# Addon-mapleCUx_HM-RFM69-RFM95-V12-001.net
KiCad netlist of a schematic drawn in EAGLE
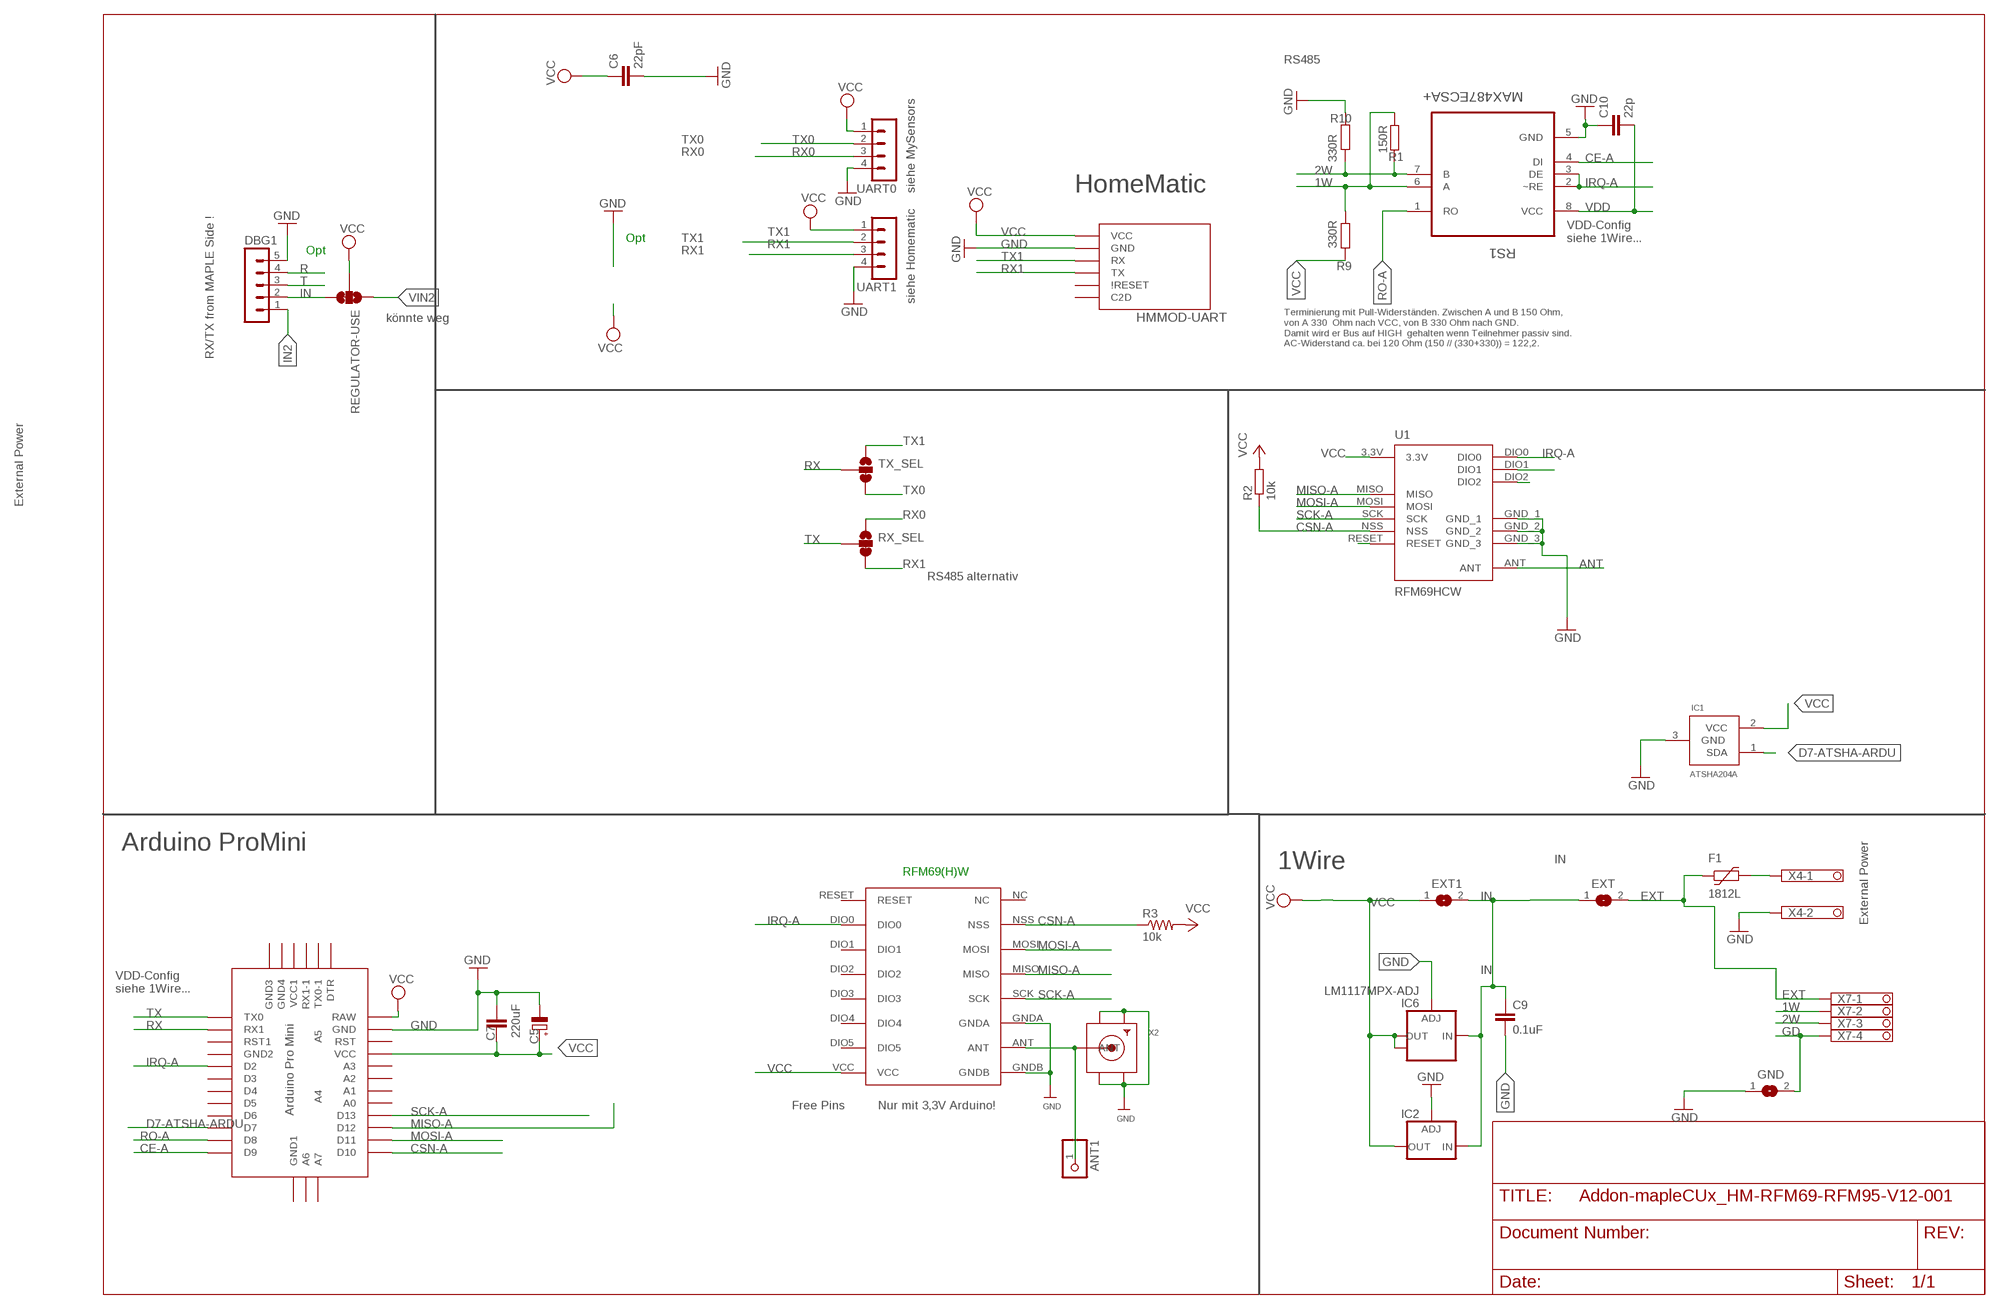
[diagram p0: schematic, sheet 1]

(export (version "E")
  (design (tool "Eeschema 10.0.6"))
  (components
    (comp (ref "ANT1")
      (value "PINHD-1X1")
      (footprint "eagle-import:1X01")
      (libsource (lib "eagle-import") (part "PINHD-1X1"))
    )
    (comp (ref "C5")
      (value "220uF")
      (footprint "eagle-import:E5-8,5")
      (libsource (lib "eagle-import") (part "CPOL-EUE5-8.5"))
    )
    (comp (ref "C6")
      (value "22pF")
      (footprint "eagle-import:C0805")
      (libsource (lib "eagle-import") (part "C-EUC0805"))
    )
    (comp (ref "C7")
      (value "C-EUC1812")
      (footprint "eagle-import:C1812")
      (libsource (lib "eagle-import") (part "C-EUC1812"))
    )
    (comp (ref "C9")
      (value "0.1uF")
      (footprint "eagle-import:C1206")
      (libsource (lib "eagle-import") (part "C-EUC1206"))
    )
    (comp (ref "C10")
      (value "22p")
      (footprint "eagle-import:C0805")
      (libsource (lib "eagle-import") (part "C-EUC0805"))
    )
    (comp (ref "DBG1")
      (value "MA05-1")
      (footprint "eagle-import:MA05-1")
      (libsource (lib "eagle-import") (part "MA05-1"))
    )
    (comp (ref "EXT") (value "SJ") (footprint "eagle-import:SJ") (libsource (lib "eagle-import") (part "SJ")))
    (comp (ref "EXT1")
      (value "SJ")
      (footprint "eagle-import:SJ")
      (libsource (lib "eagle-import") (part "SJ"))
    )
    (comp (ref "F1")
      (value "1812L")
      (footprint "eagle-import:1812L")
      (libsource (lib "eagle-import") (part "1812L"))
    )
    (comp (ref "GND") (value "SJ") (footprint "eagle-import:SJ") (libsource (lib "eagle-import") (part "SJ")))
    (comp (ref "HMMOD-UART")
      (value "HM-MOD-UARTDIL")
      (footprint "eagle-import:HM-MOD-UART-DIL")
      (libsource (lib "eagle-import") (part "HM-MOD-UARTDIL"))
    )
    (comp (ref "IC1")
      (value "ATSHA204A")
      (footprint "eagle-import:SOT23")
      (libsource (lib "eagle-import") (part "ATSHA204A"))
    )
    (comp (ref "IC2")
      (value "LD117ADT50TR")
      (footprint "eagle-import:DPACK")
      (libsource (lib "eagle-import") (part "LD117A?DT50TR"))
    )
    (comp (ref "IC6")
      (value "LM1117MPX-ADJ")
      (footprint "eagle-import:SOT223")
      (libsource (lib "eagle-import") (part "LM1117MPX-ADJ"))
    )
    (comp (ref "R1")
      (value "150R")
      (footprint "eagle-import:R0805")
      (libsource (lib "eagle-import") (part "R-EU_R0805"))
    )
    (comp (ref "R2")
      (value "10k")
      (footprint "eagle-import:M0805")
      (libsource (lib "eagle-import") (part "R-EU_M0805"))
    )
    (comp (ref "R3")
      (value "10k")
      (footprint "eagle-import:0805")
      (libsource (lib "eagle-import") (part "RESISTOR0805-RES"))
    )
    (comp (ref "R9")
      (value "330R")
      (footprint "eagle-import:R0805")
      (libsource (lib "eagle-import") (part "R-EU_R0805"))
    )
    (comp (ref "R10")
      (value "330R")
      (footprint "eagle-import:R0805")
      (libsource (lib "eagle-import") (part "R-EU_R0805"))
    )
    (comp (ref "REGULATOR-USE")
      (value "JUMPER-SMT_3_1-NC_TRACE_SILK")
      (footprint "eagle-import:SMT-JUMPER_3_1-NC_TRACE_SILK")
      (libsource (lib "eagle-import") (part "JUMPER-SMT_3_1-NC_TRACE_SILK"))
    )
    (comp (ref "RFM69W")
      (value "RFM69HW")
      (footprint "eagle-import:RFM")
      (libsource (lib "eagle-import") (part "RFM69HW"))
    )
    (comp (ref "RS1")
      (value "MAX487ECSA+")
      (footprint "eagle-import:SOIC127P600X175-8N")
      (libsource (lib "eagle-import") (part "MAX487ECSA+"))
    )
    (comp (ref "RX_SEL")
      (value "JUMPER-SMT_3_1-NC_TRACE_SILK")
      (footprint "eagle-import:SMT-JUMPER_3_1-NC_TRACE_SILK")
      (libsource (lib "eagle-import") (part "JUMPER-SMT_3_1-NC_TRACE_SILK"))
    )
    (comp (ref "TX_SEL")
      (value "JUMPER-SMT_3_1-NC_TRACE_SILK")
      (footprint "eagle-import:SMT-JUMPER_3_1-NC_TRACE_SILK")
      (libsource (lib "eagle-import") (part "JUMPER-SMT_3_1-NC_TRACE_SILK"))
    )
    (comp (ref "U$2")
      (value "ABK-PRO-MINI")
      (footprint "eagle-import:ABK-PRO-MINI")
      (libsource (lib "eagle-import") (part "ABK-PRO-MINI"))
    )
    (comp (ref "U1")
      (value "RFM69HCW")
      (footprint "eagle-import:RFM69HCW-XXXS2")
      (libsource (lib "eagle-import") (part "RFM69HCW"))
    )
    (comp (ref "UART0")
      (value "MA04-1")
      (footprint "eagle-import:MA04-1")
      (libsource (lib "eagle-import") (part "MA04-1"))
    )
    (comp (ref "UART1")
      (value "MA04-1")
      (footprint "eagle-import:MA04-1")
      (libsource (lib "eagle-import") (part "MA04-1"))
    )
    (comp (ref "X2")
      (value "SMACONNECTOR_EDGE")
      (footprint "eagle-import:SMA_EDGELAUNCH")
      (libsource (lib "eagle-import") (part "SMACONNECTOR_EDGE"))
    )
    (comp (ref "X4")
      (value "1751248")
      (footprint "eagle-import:1751248")
      (libsource (lib "eagle-import") (part "1751248"))
    )
    (comp (ref "X7")
      (value "1751264")
      (footprint "eagle-import:1751264")
      (libsource (lib "eagle-import") (part "1751264"))
    )
  )
  (nets
    (net (code "1") (name "/1W") (class "Default")
      (node (ref "R1") (pin "1") (pinfunction "1_1") (pintype "passive"))
      (node (ref "R9") (pin "2") (pinfunction "2_2") (pintype "passive"))
      (node (ref "RS1") (pin "6") (pinfunction "A_6") (pintype "bidirectional"))
      (node (ref "X7") (pin "2") (pinfunction "K_2") (pintype "passive"))
    )
    (net (code "2") (name "/2W") (class "Default")
      (node (ref "R1") (pin "2") (pinfunction "2_2") (pintype "passive"))
      (node (ref "R10") (pin "1") (pinfunction "1_1") (pintype "passive"))
      (node (ref "RS1") (pin "7") (pinfunction "B_7") (pintype "bidirectional"))
      (node (ref "X7") (pin "3") (pinfunction "K_3") (pintype "passive"))
    )
    (net (code "3") (name "/ANT") (class "Default")
      (node (ref "ANT1") (pin "1") (pinfunction "1_1") (pintype "passive"))
      (node (ref "RFM69W") (pin "ANT") (pinfunction "ANT_ANT") (pintype "bidirectional"))
      (node (ref "U1") (pin "ANT") (pinfunction "ANT_ANT") (pintype "passive"))
      (node (ref "X2") (pin "P") (pinfunction "ANT_P") (pintype "bidirectional"))
    )
    (net (code "4") (name "/CE-A") (class "Default")
      (node (ref "RS1") (pin "4") (pinfunction "DI_4") (pintype "input"))
      (node (ref "U$2") (pin "D9") (pinfunction "D9_D9") (pintype "bidirectional"))
    )
    (net (code "5") (name "/CSN-A") (class "Default")
      (node (ref "R2") (pin "1") (pinfunction "1_1") (pintype "passive"))
      (node (ref "R3") (pin "1") (pinfunction "1_1") (pintype "passive"))
      (node (ref "RFM69W") (pin "NSS") (pinfunction "NSS_NSS") (pintype "bidirectional"))
      (node (ref "U$2") (pin "D10") (pinfunction "D10_D10") (pintype "bidirectional"))
      (node (ref "U1") (pin "NSS") (pinfunction "NSS_NSS") (pintype "input"))
    )
    (net (code "6") (name "/EXT") (class "Default")
      (node (ref "EXT") (pin "2") (pinfunction "2_2") (pintype "passive"))
      (node (ref "F1") (pin "P$1") (pinfunction "1_P$1") (pintype "passive"))
      (node (ref "X7") (pin "1") (pinfunction "K_1") (pintype "passive"))
    )
    (net (code "7") (name "/GD") (class "Default")
      (node (ref "GND") (pin "2") (pinfunction "2_2") (pintype "passive"))
      (node (ref "X7") (pin "4") (pinfunction "K_4") (pintype "passive"))
    )
    (net (code "8") (name "/IN") (class "Default")
      (node (ref "C9") (pin "1") (pinfunction "1_1") (pintype "passive"))
      (node (ref "DBG1") (pin "2") (pinfunction "2_2") (pintype "passive"))
      (node (ref "EXT") (pin "1") (pinfunction "1_1") (pintype "passive"))
      (node (ref "EXT1") (pin "2") (pinfunction "2_2") (pintype "passive"))
      (node (ref "IC2") (pin "3") (pinfunction "IN_3") (pintype "input"))
      (node (ref "IC6") (pin "3") (pinfunction "IN_3") (pintype "input"))
      (node (ref "REGULATOR-USE") (pin "3") (pinfunction "3_3") (pintype "passive"))
    )
    (net (code "9") (name "/IRQ-A") (class "Default")
      (node (ref "RFM69W") (pin "DIO0") (pinfunction "DIO0_DIO0") (pintype "bidirectional"))
      (node (ref "RS1") (pin "2") (pinfunction "~{RE}_2") (pintype "input"))
      (node (ref "RS1") (pin "3") (pinfunction "DE_3") (pintype "input"))
      (node (ref "U$2") (pin "D2") (pinfunction "D2_D2") (pintype "bidirectional"))
      (node (ref "U1") (pin "DIO0") (pinfunction "DIO0_DIO0") (pintype "bidirectional"))
    )
    (net (code "10") (name "/MISO-A") (class "Default")
      (node (ref "RFM69W") (pin "MISO") (pinfunction "MISO_MISO") (pintype "bidirectional"))
      (node (ref "U$2") (pin "D12") (pinfunction "D12_D12") (pintype "bidirectional"))
      (node (ref "U1") (pin "MISO") (pinfunction "MISO_MISO") (pintype "bidirectional"))
    )
    (net (code "11") (name "/MOSI-A") (class "Default")
      (node (ref "RFM69W") (pin "MOSI") (pinfunction "MOSI_MOSI") (pintype "bidirectional"))
      (node (ref "U$2") (pin "D11") (pinfunction "D11_D11") (pintype "bidirectional"))
      (node (ref "U1") (pin "MOSI") (pinfunction "MOSI_MOSI") (pintype "input"))
    )
    (net (code "12") (name "/R") (class "Default")
      (node (ref "DBG1") (pin "4") (pinfunction "4_4") (pintype "passive"))
    )
    (net (code "13") (name "/RX") (class "Default")
      (node (ref "TX_SEL") (pin "2") (pinfunction "2_2") (pintype "passive"))
      (node (ref "U$2") (pin "RX1") (pinfunction "RX1_RX1") (pintype "bidirectional"))
    )
    (net (code "14") (name "/RX0") (class "Default")
      (node (ref "RX_SEL") (pin "1") (pinfunction "1_1") (pintype "passive"))
      (node (ref "UART0") (pin "3") (pinfunction "3_3") (pintype "passive"))
    )
    (net (code "15") (name "/RX1") (class "Default")
      (node (ref "HMMOD-UART") (pin "5") (pinfunction "TX_5") (pintype "bidirectional"))
      (node (ref "RX_SEL") (pin "3") (pinfunction "3_3") (pintype "passive"))
      (node (ref "UART1") (pin "3") (pinfunction "3_3") (pintype "passive"))
    )
    (net (code "16") (name "/SCK-A") (class "Default")
      (node (ref "RFM69W") (pin "SCK") (pinfunction "SCK_SCK") (pintype "bidirectional"))
      (node (ref "U$2") (pin "D13") (pinfunction "D13_D13") (pintype "bidirectional"))
      (node (ref "U1") (pin "SCK") (pinfunction "SCK_SCK") (pintype "input"))
    )
    (net (code "17") (name "/T") (class "Default")
      (node (ref "DBG1") (pin "3") (pinfunction "3_3") (pintype "passive"))
    )
    (net (code "18") (name "/TX") (class "Default")
      (node (ref "RX_SEL") (pin "2") (pinfunction "2_2") (pintype "passive"))
      (node (ref "U$2") (pin "TX0") (pinfunction "TX0_TX0") (pintype "bidirectional"))
    )
    (net (code "19") (name "/TX0") (class "Default")
      (node (ref "TX_SEL") (pin "3") (pinfunction "3_3") (pintype "passive"))
      (node (ref "UART0") (pin "2") (pinfunction "2_2") (pintype "passive"))
    )
    (net (code "20") (name "/TX1") (class "Default")
      (node (ref "HMMOD-UART") (pin "6") (pinfunction "RX_6") (pintype "bidirectional"))
      (node (ref "TX_SEL") (pin "1") (pinfunction "1_1") (pintype "passive"))
      (node (ref "UART1") (pin "2") (pinfunction "2_2") (pintype "passive"))
    )
    (net (code "21") (name "/VDD") (class "Default")
      (node (ref "C10") (pin "2") (pinfunction "2_2") (pintype "passive"))
      (node (ref "RS1") (pin "8") (pinfunction "VCC_8") (pintype "power_in"))
    )
    (net (code "22") (name "D7-ATSHA-ARDU") (class "Default")
      (node (ref "IC1") (pin "1") (pinfunction "SDA_1") (pintype "bidirectional"))
      (node (ref "U$2") (pin "D7") (pinfunction "D7_D7") (pintype "bidirectional"))
    )
    (net (code "23") (name "GND") (class "Default")
      (node (ref "C10") (pin "1") (pinfunction "1_1") (pintype "passive"))
      (node (ref "C5") (pin "-") (pinfunction "-_-") (pintype "passive"))
      (node (ref "C6") (pin "2") (pinfunction "2_2") (pintype "passive"))
      (node (ref "C7") (pin "1") (pinfunction "1_1") (pintype "passive"))
      (node (ref "C9") (pin "2") (pinfunction "2_2") (pintype "passive"))
      (node (ref "DBG1") (pin "5") (pinfunction "5_5") (pintype "passive"))
      (node (ref "GND") (pin "1") (pinfunction "1_1") (pintype "passive"))
      (node (ref "HMMOD-UART") (pin "2") (pinfunction "GND_2") (pintype "power_in"))
      (node (ref "IC1") (pin "3") (pinfunction "GND_3") (pintype "bidirectional"))
      (node (ref "IC2") (pin "1") (pinfunction "ADJ_1") (pintype "input"))
      (node (ref "IC6") (pin "1") (pinfunction "ADJ_1") (pintype "input"))
      (node (ref "R10") (pin "2") (pinfunction "2_2") (pintype "passive"))
      (node (ref "RFM69W") (pin "GNDA") (pinfunction "GNDA_GNDA") (pintype "bidirectional"))
      (node (ref "RFM69W") (pin "GNDB") (pinfunction "GNDB_GNDB") (pintype "bidirectional"))
      (node (ref "RS1") (pin "5") (pinfunction "GND_5") (pintype "passive"))
      (node (ref "U$2") (pin "GND") (pinfunction "GND_GND") (pintype "bidirectional"))
      (node (ref "U1") (pin "GND_1") (pinfunction "GND_1_GND_1") (pintype "power_in"))
      (node (ref "U1") (pin "GND_2") (pinfunction "GND_2_GND_2") (pintype "power_in"))
      (node (ref "U1") (pin "GND_3") (pinfunction "GND_3_GND_3") (pintype "power_in"))
      (node (ref "UART0") (pin "4") (pinfunction "4_4") (pintype "passive"))
      (node (ref "UART1") (pin "4") (pinfunction "4_4") (pintype "passive"))
      (node (ref "X2") (pin "GND@1") (pinfunction "GND4_GND@1") (pintype "power_in"))
      (node (ref "X2") (pin "GND@2") (pinfunction "GND3_GND@2") (pintype "power_in"))
      (node (ref "X2") (pin "GND@3") (pinfunction "GND2_GND@3") (pintype "power_in"))
      (node (ref "X2") (pin "GND@4") (pinfunction "GND1_GND@4") (pintype "power_in"))
      (node (ref "X4") (pin "2") (pinfunction "K_2") (pintype "passive"))
    )
    (net (code "24") (name "IN2") (class "Default")
      (node (ref "DBG1") (pin "1") (pinfunction "1_1") (pintype "passive"))
    )
    (net (code "25") (name "Net-(F1-2)") (class "Default")
      (node (ref "F1") (pin "P$2") (pinfunction "2_P$2") (pintype "passive"))
      (node (ref "X4") (pin "1") (pinfunction "K_1") (pintype "passive"))
    )
    (net (code "26") (name "RO-A") (class "Default")
      (node (ref "RS1") (pin "1") (pinfunction "RO_1") (pintype "output"))
      (node (ref "U$2") (pin "D8") (pinfunction "D8_D8") (pintype "bidirectional"))
    )
    (net (code "27") (name "VCC") (class "Default")
      (node (ref "C5") (pin "+") (pinfunction "+_+") (pintype "passive"))
      (node (ref "C6") (pin "1") (pinfunction "1_1") (pintype "passive"))
      (node (ref "C7") (pin "2") (pinfunction "2_2") (pintype "passive"))
      (node (ref "EXT1") (pin "1") (pinfunction "1_1") (pintype "passive"))
      (node (ref "HMMOD-UART") (pin "1") (pinfunction "VCC_1") (pintype "power_in"))
      (node (ref "IC1") (pin "2") (pinfunction "VCC_2") (pintype "bidirectional"))
      (node (ref "IC2") (pin "4") (pinfunction "OUT_4") (pintype "passive"))
      (node (ref "IC6") (pin "2") (pinfunction "OUT_2") (pintype "passive"))
      (node (ref "IC6") (pin "TAB") (pinfunction "OUT1_TAB") (pintype "passive"))
      (node (ref "R2") (pin "2") (pinfunction "2_2") (pintype "passive"))
      (node (ref "R3") (pin "2") (pinfunction "2_2") (pintype "passive"))
      (node (ref "R9") (pin "1") (pinfunction "1_1") (pintype "passive"))
      (node (ref "REGULATOR-USE") (pin "2") (pinfunction "2_2") (pintype "passive"))
      (node (ref "RFM69W") (pin "VCC") (pinfunction "VCC_VCC") (pintype "bidirectional"))
      (node (ref "U$2") (pin "RAW") (pinfunction "RAW_RAW") (pintype "bidirectional"))
      (node (ref "U$2") (pin "VCC") (pinfunction "VCC_VCC") (pintype "bidirectional"))
      (node (ref "U1") (pin "3.3V") (pinfunction "3.3V_3.3V") (pintype "power_in"))
      (node (ref "UART0") (pin "1") (pinfunction "1_1") (pintype "passive"))
      (node (ref "UART1") (pin "1") (pinfunction "1_1") (pintype "passive"))
    )
    (net (code "28") (name "VIN2") (class "Default")
      (node (ref "REGULATOR-USE") (pin "1") (pinfunction "1_1") (pintype "passive"))
    )
    (net (code "29") (name "unconnected-(HMMOD-UART-C2D-Pad3)") (class "Default")
      (node (ref "HMMOD-UART") (pin "3") (pinfunction "C2D_3") (pintype "bidirectional"))
    )
    (net (code "30") (name "unconnected-(HMMOD-UART-\\~{RESET}-Pad4)") (class "Default")
      (node (ref "HMMOD-UART") (pin "4") (pinfunction "\\~{RESET}_4") (pintype "bidirectional"))
    )
    (net (code "31") (name "unconnected-(RFM69W-PadDIO1)") (class "Default")
      (node (ref "RFM69W") (pin "DIO1") (pinfunction "DIO1_DIO1") (pintype "bidirectional"))
    )
    (net (code "32") (name "unconnected-(RFM69W-PadDIO2)") (class "Default")
      (node (ref "RFM69W") (pin "DIO2") (pinfunction "DIO2_DIO2") (pintype "bidirectional"))
    )
    (net (code "33") (name "unconnected-(RFM69W-PadDIO3)") (class "Default")
      (node (ref "RFM69W") (pin "DIO3") (pinfunction "DIO3_DIO3") (pintype "bidirectional"))
    )
    (net (code "34") (name "unconnected-(RFM69W-PadDIO4)") (class "Default")
      (node (ref "RFM69W") (pin "DIO4") (pinfunction "DIO4_DIO4") (pintype "bidirectional"))
    )
    (net (code "35") (name "unconnected-(RFM69W-PadDIO5)") (class "Default")
      (node (ref "RFM69W") (pin "DIO5") (pinfunction "DIO5_DIO5") (pintype "bidirectional"))
    )
    (net (code "36") (name "unconnected-(RFM69W-PadNC)") (class "Default")
      (node (ref "RFM69W") (pin "NC") (pinfunction "NC_NC") (pintype "bidirectional"))
    )
    (net (code "37") (name "unconnected-(RFM69W-PadRESET)") (class "Default")
      (node (ref "RFM69W") (pin "RESET") (pinfunction "RESET_RESET") (pintype "bidirectional"))
    )
    (net (code "38") (name "unconnected-(U$2-GND1-PadGND4)") (class "Default")
      (node (ref "U$2") (pin "GND4") (pinfunction "GND1_GND4") (pintype "bidirectional"))
    )
    (net (code "39") (name "unconnected-(U$2-GND2-PadGND1)") (class "Default")
      (node (ref "U$2") (pin "GND1") (pinfunction "GND2_GND1") (pintype "bidirectional"))
    )
    (net (code "40") (name "unconnected-(U$2-GND3-PadGND2)") (class "Default")
      (node (ref "U$2") (pin "GND2") (pinfunction "GND3_GND2") (pintype "bidirectional"))
    )
    (net (code "41") (name "unconnected-(U$2-GND4-PadGND3)") (class "Default")
      (node (ref "U$2") (pin "GND3") (pinfunction "GND4_GND3") (pintype "bidirectional"))
    )
    (net (code "42") (name "unconnected-(U$2-PadA0)") (class "Default")
      (node (ref "U$2") (pin "A0") (pinfunction "A0_A0") (pintype "bidirectional"))
    )
    (net (code "43") (name "unconnected-(U$2-PadA1)") (class "Default")
      (node (ref "U$2") (pin "A1") (pinfunction "A1_A1") (pintype "bidirectional"))
    )
    (net (code "44") (name "unconnected-(U$2-PadA2)") (class "Default")
      (node (ref "U$2") (pin "A2") (pinfunction "A2_A2") (pintype "bidirectional"))
    )
    (net (code "45") (name "unconnected-(U$2-PadA3)") (class "Default")
      (node (ref "U$2") (pin "A3") (pinfunction "A3_A3") (pintype "bidirectional"))
    )
    (net (code "46") (name "unconnected-(U$2-PadA4)") (class "Default")
      (node (ref "U$2") (pin "A4") (pinfunction "A4_A4") (pintype "bidirectional"))
    )
    (net (code "47") (name "unconnected-(U$2-PadA5)") (class "Default")
      (node (ref "U$2") (pin "A5") (pinfunction "A5_A5") (pintype "bidirectional"))
    )
    (net (code "48") (name "unconnected-(U$2-PadA6)") (class "Default")
      (node (ref "U$2") (pin "A6") (pinfunction "A6_A6") (pintype "bidirectional"))
    )
    (net (code "49") (name "unconnected-(U$2-PadA7)") (class "Default")
      (node (ref "U$2") (pin "A7") (pinfunction "A7_A7") (pintype "bidirectional"))
    )
    (net (code "50") (name "unconnected-(U$2-PadD3)") (class "Default")
      (node (ref "U$2") (pin "D3") (pinfunction "D3_D3") (pintype "bidirectional"))
    )
    (net (code "51") (name "unconnected-(U$2-PadD4)") (class "Default")
      (node (ref "U$2") (pin "D4") (pinfunction "D4_D4") (pintype "bidirectional"))
    )
    (net (code "52") (name "unconnected-(U$2-PadD5)") (class "Default")
      (node (ref "U$2") (pin "D5") (pinfunction "D5_D5") (pintype "bidirectional"))
    )
    (net (code "53") (name "unconnected-(U$2-PadD6)") (class "Default")
      (node (ref "U$2") (pin "D6") (pinfunction "D6_D6") (pintype "bidirectional"))
    )
    (net (code "54") (name "unconnected-(U$2-PadDTR)") (class "Default")
      (node (ref "U$2") (pin "DTR") (pinfunction "DTR_DTR") (pintype "bidirectional"))
    )
    (net (code "55") (name "unconnected-(U$2-PadRST)") (class "Default")
      (node (ref "U$2") (pin "RST") (pinfunction "RST_RST") (pintype "bidirectional"))
    )
    (net (code "56") (name "unconnected-(U$2-PadRST1)") (class "Default")
      (node (ref "U$2") (pin "RST1") (pinfunction "RST1_RST1") (pintype "bidirectional"))
    )
    (net (code "57") (name "unconnected-(U$2-PadRX1-1)") (class "Default")
      (node (ref "U$2") (pin "RX1-1") (pinfunction "RX1-1_RX1-1") (pintype "bidirectional"))
    )
    (net (code "58") (name "unconnected-(U$2-PadTX0-1)") (class "Default")
      (node (ref "U$2") (pin "TX0-1") (pinfunction "TX0-1_TX0-1") (pintype "bidirectional"))
    )
    (net (code "59") (name "unconnected-(U$2-PadVCC1)") (class "Default")
      (node (ref "U$2") (pin "VCC1") (pinfunction "VCC1_VCC1") (pintype "bidirectional"))
    )
    (net (code "60") (name "unconnected-(U1-PadDIO1)") (class "Default")
      (node (ref "U1") (pin "DIO1") (pinfunction "DIO1_DIO1") (pintype "bidirectional"))
    )
    (net (code "61") (name "unconnected-(U1-PadDIO2)") (class "Default")
      (node (ref "U1") (pin "DIO2") (pinfunction "DIO2_DIO2") (pintype "bidirectional"))
    )
    (net (code "62") (name "unconnected-(U1-PadRESET)") (class "Default")
      (node (ref "U1") (pin "RESET") (pinfunction "RESET_RESET") (pintype "input"))
    )
  )
)
